# AFE.net
KiCad netlist of a schematic drawn in Altium Designer
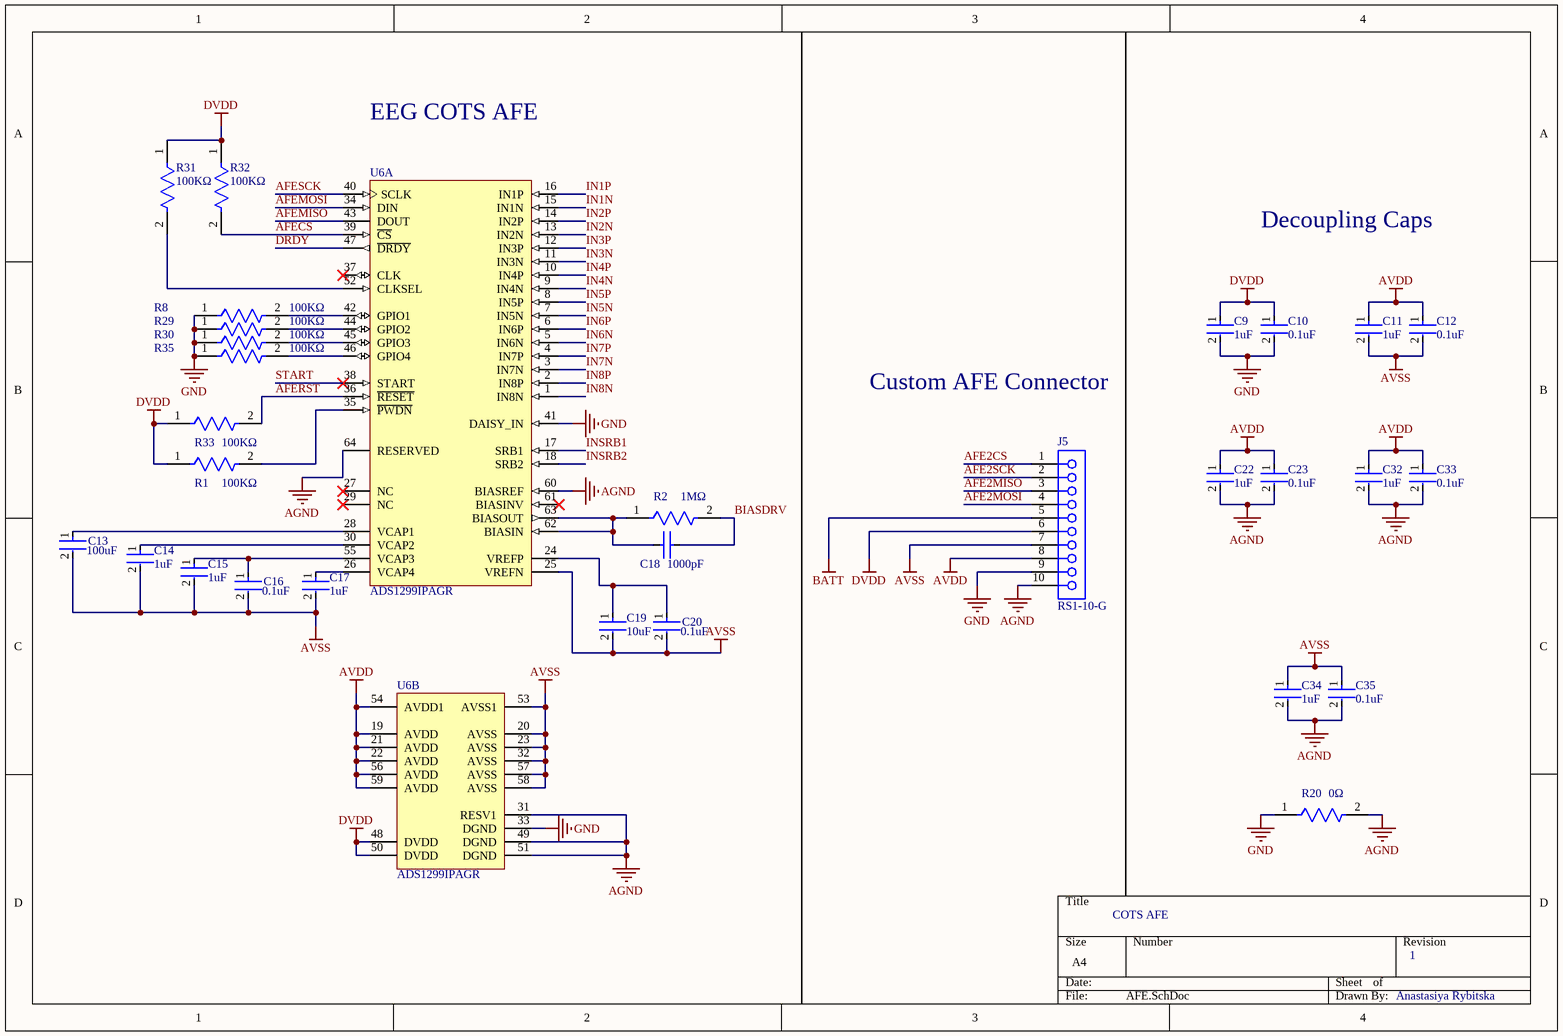
[diagram p0: AFE.SchDoc]

(export (version "E")
  (design (tool "Eeschema 10.0.6"))
  (components
    (comp (ref "C9")
      (value "CL10A105KA8NNNC")
      (footprint "FP-CL10-IPC_C")
      (description "Cap Ceramic 1uF 25V X5R ±10% Pad SMD 0603 +85°C T/R")
      (fields
        (field (name "CAPACITANCE") "1uF")
        (field (name "VOLTAGE") "25V")
        (field (name "TOLERANCE") "10%")
      )
      (libsource (lib "Altium Content Vault") (part "b4654b650e69147ec39a6b967a45e02"))
    )
    (comp (ref "C10")
      (value "KGM15BR71H104JT")
      (footprint "FP-0603-L_1_6_0_15-W_0_81-MFG")
      (description "KGM15BR71H104JT Cap Cer 0.1UF 50V X7R 0603")
      (fields (field (name "CAPACITANCE") "0.1uF") (field (name "TOLERANCE") "5%"))
      (libsource (lib "Altium Content Vault") (part "b4654b650e69147ec39a6b967a45e02"))
    )
    (comp (ref "C11")
      (value "CL10A105KA8NNNC")
      (footprint "FP-CL10-IPC_C")
      (description "Cap Ceramic 1uF 25V X5R ±10% Pad SMD 0603 +85°C T/R")
      (fields
        (field (name "CAPACITANCE") "1uF")
        (field (name "VOLTAGE") "25V")
        (field (name "TOLERANCE") "10%")
      )
      (libsource (lib "Altium Content Vault") (part "b4654b650e69147ec39a6b967a45e02"))
    )
    (comp (ref "C12")
      (value "KGM15BR71H104JT")
      (footprint "FP-0603-L_1_6_0_15-W_0_81-MFG")
      (description "KGM15BR71H104JT Cap Cer 0.1UF 50V X7R 0603")
      (fields (field (name "CAPACITANCE") "0.1uF") (field (name "TOLERANCE") "5%"))
      (libsource (lib "Altium Content Vault") (part "b4654b650e69147ec39a6b967a45e02"))
    )
    (comp (ref "C13")
      (value "GRM21BR60E107ME15K")
      (footprint "FP-GRM21B-0_2-e0_2_0_7-IPC_A")
      (description "Chip Multilayer Ceramic Capacitors for General Purpose, 0805, 100uF, X5R, 15%, 20%, 2.5V")
      (fields (field (name "CAPACITANCE") "100uF") (field (name "TOLERANCE") "20%"))
      (libsource (lib "Altium Content Vault") (part "b4654b650e69147ec39a6b967a45e02"))
    )
    (comp (ref "C14")
      (value "CL10A105KA8NNNC")
      (footprint "FP-CL10-IPC_C")
      (description "Cap Ceramic 1uF 25V X5R ±10% Pad SMD 0603 +85°C T/R")
      (fields
        (field (name "CAPACITANCE") "1uF")
        (field (name "VOLTAGE") "25V")
        (field (name "TOLERANCE") "10%")
      )
      (libsource (lib "Altium Content Vault") (part "b4654b650e69147ec39a6b967a45e02"))
    )
    (comp (ref "C15")
      (value "CL10A105KA8NNNC")
      (footprint "FP-CL10-IPC_C")
      (description "Cap Ceramic 1uF 25V X5R ±10% Pad SMD 0603 +85°C T/R")
      (fields
        (field (name "CAPACITANCE") "1uF")
        (field (name "VOLTAGE") "25V")
        (field (name "TOLERANCE") "10%")
      )
      (libsource (lib "Altium Content Vault") (part "b4654b650e69147ec39a6b967a45e02"))
    )
    (comp (ref "C16")
      (value "KGM15BR71H104JT")
      (footprint "FP-0603-L_1_6_0_15-W_0_81-MFG")
      (description "KGM15BR71H104JT Cap Cer 0.1UF 50V X7R 0603")
      (fields (field (name "CAPACITANCE") "0.1uF") (field (name "TOLERANCE") "5%"))
      (libsource (lib "Altium Content Vault") (part "b4654b650e69147ec39a6b967a45e02"))
    )
    (comp (ref "C17")
      (value "CL10A105KA8NNNC")
      (footprint "FP-CL10-IPC_C")
      (description "Cap Ceramic 1uF 25V X5R ±10% Pad SMD 0603 +85°C T/R")
      (fields
        (field (name "CAPACITANCE") "1uF")
        (field (name "VOLTAGE") "25V")
        (field (name "TOLERANCE") "10%")
      )
      (libsource (lib "Altium Content Vault") (part "b4654b650e69147ec39a6b967a45e02"))
    )
    (comp (ref "C18")
      (value "0603N102F500CT")
      (footprint "CAP_0603_S_WAL")
      (description "No Description Available")
      (fields
        (field (name "CAPACITANCE") "1000pF")
        (field (name "COPYRIGHT") "Copyright (C) 2023 Ultra Librarian. All rights reserved.")
      )
      (libsource (lib "Schlib1") (part "0603N102F500CT"))
    )
    (comp (ref "C19")
      (value "CL10A106MQ8NNNC")
      (footprint "FP-CL10-IPC_C")
      (description "Cap Ceramic 10uF 6.3V X5R ±20% Pad SMD 0603 +85°C T/R")
      (fields
        (field (name "CAPACITANCE") "10uF")
        (field (name "VOLTAGE") "6.3V")
        (field (name "TOLERANCE") "20%")
      )
      (libsource (lib "Altium Content Vault") (part "b4654b650e69147ec39a6b967a45e02"))
    )
    (comp (ref "C20")
      (value "KGM15BR71H104JT")
      (footprint "FP-0603-L_1_6_0_15-W_0_81-MFG")
      (description "KGM15BR71H104JT Cap Cer 0.1UF 50V X7R 0603")
      (fields (field (name "CAPACITANCE") "0.1uF") (field (name "TOLERANCE") "5%"))
      (libsource (lib "Altium Content Vault") (part "b4654b650e69147ec39a6b967a45e02"))
    )
    (comp (ref "C22")
      (value "CL10A105KA8NNNC")
      (footprint "FP-CL10-IPC_C")
      (description "Cap Ceramic 1uF 25V X5R ±10% Pad SMD 0603 +85°C T/R")
      (fields
        (field (name "CAPACITANCE") "1uF")
        (field (name "VOLTAGE") "25V")
        (field (name "TOLERANCE") "10%")
      )
      (libsource (lib "Altium Content Vault") (part "b4654b650e69147ec39a6b967a45e02"))
    )
    (comp (ref "C23")
      (value "KGM15BR71H104JT")
      (footprint "FP-0603-L_1_6_0_15-W_0_81-MFG")
      (description "KGM15BR71H104JT Cap Cer 0.1UF 50V X7R 0603")
      (fields (field (name "CAPACITANCE") "0.1uF") (field (name "TOLERANCE") "5%"))
      (libsource (lib "Altium Content Vault") (part "b4654b650e69147ec39a6b967a45e02"))
    )
    (comp (ref "C32")
      (value "CL10A105KA8NNNC")
      (footprint "FP-CL10-IPC_C")
      (description "Cap Ceramic 1uF 25V X5R ±10% Pad SMD 0603 +85°C T/R")
      (fields
        (field (name "CAPACITANCE") "1uF")
        (field (name "VOLTAGE") "25V")
        (field (name "TOLERANCE") "10%")
      )
      (libsource (lib "Altium Content Vault") (part "b4654b650e69147ec39a6b967a45e02"))
    )
    (comp (ref "C33")
      (value "KGM15BR71H104JT")
      (footprint "FP-0603-L_1_6_0_15-W_0_81-MFG")
      (description "KGM15BR71H104JT Cap Cer 0.1UF 50V X7R 0603")
      (fields (field (name "CAPACITANCE") "0.1uF") (field (name "TOLERANCE") "5%"))
      (libsource (lib "Altium Content Vault") (part "b4654b650e69147ec39a6b967a45e02"))
    )
    (comp (ref "C34")
      (value "CL10A105KA8NNNC")
      (footprint "FP-CL10-IPC_C")
      (description "Cap Ceramic 1uF 25V X5R ±10% Pad SMD 0603 +85°C T/R")
      (fields
        (field (name "CAPACITANCE") "1uF")
        (field (name "VOLTAGE") "25V")
        (field (name "TOLERANCE") "10%")
      )
      (libsource (lib "Altium Content Vault") (part "b4654b650e69147ec39a6b967a45e02"))
    )
    (comp (ref "C35")
      (value "KGM15BR71H104JT")
      (footprint "FP-0603-L_1_6_0_15-W_0_81-MFG")
      (description "KGM15BR71H104JT Cap Cer 0.1UF 50V X7R 0603")
      (fields (field (name "CAPACITANCE") "0.1uF") (field (name "TOLERANCE") "5%"))
      (libsource (lib "Altium Content Vault") (part "b4654b650e69147ec39a6b967a45e02"))
    )
    (comp (ref "J5")
      (value "RS1-10-G")
      (footprint "61301011821")
      (libsource (lib "Altium Content Vault") (part "Header_Female_1R_10P"))
    )
    (comp (ref "R1")
      (value "RMCF0603FT100K")
      (footprint "FP-RMCF0603-IPC_C")
      (description "100kΩ ±1% 0.1W 0603 Thick Film Chip Resistor AEC-Q200 compliant")
      (fields (field (name "TOLERANCE") "1%") (field (name "RESISTANCE") "100KΩ"))
      (libsource (lib "Altium Content Vault") (part "1029c3af85768c4190bb7ad29bc67b5"))
    )
    (comp (ref "R2")
      (value "ERJ-3EKF1004V")
      (footprint "FP-ERJ3EK-IPC_C")
      (description "RES SMD 1M OHM 1% 1/10W 0603")
      (fields (field (name "TOLERANCE") "1%") (field (name "RESISTANCE") "1MΩ"))
      (libsource (lib "Altium Content Vault") (part "1029c3af85768c4190bb7ad29bc67b5"))
    )
    (comp (ref "R8")
      (value "RMCF0603FT100K")
      (footprint "FP-RMCF0603-IPC_C")
      (description "100kΩ ±1% 0.1W 0603 Thick Film Chip Resistor AEC-Q200 compliant")
      (fields (field (name "TOLERANCE") "1%") (field (name "RESISTANCE") "100KΩ"))
      (libsource (lib "Altium Content Vault") (part "1029c3af85768c4190bb7ad29bc67b5"))
    )
    (comp (ref "R20")
      (value "RMCF0603ZT0R00")
      (footprint "FP-RMCF0603-MFG")
      (description "RES 0 OHM JUMPER 1/10W 0603")
      (fields
        (field (name "OCTOPART") "https://octopart.com/rmcf0603zt0r00-stackpole+electronics-19213618")
        (field (name "MANUFACTURER") "Stackpole")
        (field (name "RESISTANCE") "0Ω")
      )
      (libsource (lib "Altium Content Vault") (part "1029c3af85768c4190bb7ad29bc67b5"))
    )
    (comp (ref "R29")
      (value "RMCF0603FT100K")
      (footprint "FP-RMCF0603-IPC_C")
      (description "100kΩ ±1% 0.1W 0603 Thick Film Chip Resistor AEC-Q200 compliant")
      (fields (field (name "TOLERANCE") "1%") (field (name "RESISTANCE") "100KΩ"))
      (libsource (lib "Altium Content Vault") (part "1029c3af85768c4190bb7ad29bc67b5"))
    )
    (comp (ref "R30")
      (value "RMCF0603FT100K")
      (footprint "FP-RMCF0603-IPC_C")
      (description "100kΩ ±1% 0.1W 0603 Thick Film Chip Resistor AEC-Q200 compliant")
      (fields (field (name "TOLERANCE") "1%") (field (name "RESISTANCE") "100KΩ"))
      (libsource (lib "Altium Content Vault") (part "1029c3af85768c4190bb7ad29bc67b5"))
    )
    (comp (ref "R31")
      (value "RMCF0603FT100K")
      (footprint "FP-RMCF0603-IPC_C")
      (description "100kΩ ±1% 0.1W 0603 Thick Film Chip Resistor AEC-Q200 compliant")
      (fields (field (name "TOLERANCE") "1%") (field (name "RESISTANCE") "100KΩ"))
      (libsource (lib "Altium Content Vault") (part "1029c3af85768c4190bb7ad29bc67b5"))
    )
    (comp (ref "R32")
      (value "RMCF0603FT100K")
      (footprint "FP-RMCF0603-IPC_C")
      (description "100kΩ ±1% 0.1W 0603 Thick Film Chip Resistor AEC-Q200 compliant")
      (fields (field (name "TOLERANCE") "1%") (field (name "RESISTANCE") "100KΩ"))
      (libsource (lib "Altium Content Vault") (part "1029c3af85768c4190bb7ad29bc67b5"))
    )
    (comp (ref "R33")
      (value "RMCF0603FT100K")
      (footprint "FP-RMCF0603-IPC_C")
      (description "100kΩ ±1% 0.1W 0603 Thick Film Chip Resistor AEC-Q200 compliant")
      (fields (field (name "TOLERANCE") "1%") (field (name "RESISTANCE") "100KΩ"))
      (libsource (lib "Altium Content Vault") (part "1029c3af85768c4190bb7ad29bc67b5"))
    )
    (comp (ref "R35")
      (value "RMCF0603FT100K")
      (footprint "FP-RMCF0603-IPC_C")
      (description "100kΩ ±1% 0.1W 0603 Thick Film Chip Resistor AEC-Q200 compliant")
      (fields (field (name "TOLERANCE") "1%") (field (name "RESISTANCE") "100KΩ"))
      (libsource (lib "Altium Content Vault") (part "1029c3af85768c4190bb7ad29bc67b5"))
    )
    (comp (ref "U6")
      (value "ADS1299IPAGR")
      (footprint "PAG0064A_M")
      (fields (field (name "MANUFACTURER") "Texas Instruments"))
      (libsource (lib "Altium Content Vault") (part "TI-ADS1299-PAG-64"))
    )
  )
  (nets
    (net (code "1") (name "/AFE2CS") (class "Default")
      (node (ref "J5") (pin "1") (pinfunction "1_1") (pintype "passive"))
    )
    (net (code "2") (name "/AFE2MISO") (class "Default")
      (node (ref "J5") (pin "3") (pinfunction "3_3") (pintype "passive"))
    )
    (net (code "3") (name "/AFE2MOSI") (class "Default")
      (node (ref "J5") (pin "4") (pinfunction "4_4") (pintype "passive"))
    )
    (net (code "4") (name "/AFE2SCK") (class "Default")
      (node (ref "J5") (pin "2") (pinfunction "2_2") (pintype "passive"))
    )
    (net (code "5") (name "/AFECS") (class "Default")
      (node (ref "R32") (pin "2") (pinfunction "2_2") (pintype "passive"))
      (node (ref "U6") (pin "39") (pinfunction "~{CS}_39") (pintype "input"))
    )
    (net (code "6") (name "/AFEMISO") (class "Default")
      (node (ref "U6") (pin "43") (pinfunction "DOUT_43") (pintype "tri_state"))
    )
    (net (code "7") (name "/AFEMOSI") (class "Default")
      (node (ref "U6") (pin "34") (pinfunction "DIN_34") (pintype "input"))
    )
    (net (code "8") (name "/AFERST") (class "Default")
      (node (ref "R33") (pin "2") (pinfunction "2_2") (pintype "passive"))
      (node (ref "U6") (pin "36") (pinfunction "~{RESET}_36") (pintype "input"))
    )
    (net (code "9") (name "/AFESCK") (class "Default")
      (node (ref "U6") (pin "40") (pinfunction "SCLK_40") (pintype "input"))
    )
    (net (code "10") (name "/BIASDRV") (class "Default")
      (node (ref "C18") (pin "2") (pinfunction "2_2") (pintype "passive"))
      (node (ref "R2") (pin "2") (pinfunction "2_2") (pintype "passive"))
    )
    (net (code "11") (name "/DRDY") (class "Default")
      (node (ref "U6") (pin "47") (pinfunction "~{DRDY}_47") (pintype "output"))
    )
    (net (code "12") (name "/IN1N") (class "Default")
      (node (ref "U6") (pin "15") (pinfunction "IN1N_15") (pintype "input"))
    )
    (net (code "13") (name "/IN1P") (class "Default")
      (node (ref "U6") (pin "16") (pinfunction "IN1P_16") (pintype "input"))
    )
    (net (code "14") (name "/IN2N") (class "Default")
      (node (ref "U6") (pin "13") (pinfunction "IN2N_13") (pintype "input"))
    )
    (net (code "15") (name "/IN2P") (class "Default")
      (node (ref "U6") (pin "14") (pinfunction "IN2P_14") (pintype "input"))
    )
    (net (code "16") (name "/IN3N") (class "Default")
      (node (ref "U6") (pin "11") (pinfunction "IN3N_11") (pintype "input"))
    )
    (net (code "17") (name "/IN3P") (class "Default")
      (node (ref "U6") (pin "12") (pinfunction "IN3P_12") (pintype "input"))
    )
    (net (code "18") (name "/IN4N") (class "Default")
      (node (ref "U6") (pin "9") (pinfunction "IN4N_9") (pintype "input"))
    )
    (net (code "19") (name "/IN4P") (class "Default")
      (node (ref "U6") (pin "10") (pinfunction "IN4P_10") (pintype "input"))
    )
    (net (code "20") (name "/IN5N") (class "Default")
      (node (ref "U6") (pin "7") (pinfunction "IN5N_7") (pintype "input"))
    )
    (net (code "21") (name "/IN5P") (class "Default")
      (node (ref "U6") (pin "8") (pinfunction "IN5P_8") (pintype "input"))
    )
    (net (code "22") (name "/IN6N") (class "Default")
      (node (ref "U6") (pin "5") (pinfunction "IN6N_5") (pintype "input"))
    )
    (net (code "23") (name "/IN6P") (class "Default")
      (node (ref "U6") (pin "6") (pinfunction "IN6P_6") (pintype "input"))
    )
    (net (code "24") (name "/IN7N") (class "Default")
      (node (ref "U6") (pin "3") (pinfunction "IN7N_3") (pintype "input"))
    )
    (net (code "25") (name "/IN7P") (class "Default")
      (node (ref "U6") (pin "4") (pinfunction "IN7P_4") (pintype "input"))
    )
    (net (code "26") (name "/IN8N") (class "Default")
      (node (ref "U6") (pin "1") (pinfunction "IN8N_1") (pintype "input"))
    )
    (net (code "27") (name "/IN8P") (class "Default")
      (node (ref "U6") (pin "2") (pinfunction "IN8P_2") (pintype "input"))
    )
    (net (code "28") (name "/INSRB1") (class "Default")
      (node (ref "U6") (pin "17") (pinfunction "SRB1_17") (pintype "input"))
    )
    (net (code "29") (name "/INSRB2") (class "Default")
      (node (ref "U6") (pin "18") (pinfunction "SRB2_18") (pintype "input"))
    )
    (net (code "30") (name "/START") (class "Default")
      (node (ref "U6") (pin "38") (pinfunction "START_38") (pintype "input+no_connect"))
    )
    (net (code "31") (name "AGND") (class "Default")
      (node (ref "C22") (pin "2") (pinfunction "2_2") (pintype "passive"))
      (node (ref "C23") (pin "2") (pinfunction "2_2") (pintype "passive"))
      (node (ref "C32") (pin "2") (pinfunction "2_2") (pintype "passive"))
      (node (ref "C33") (pin "2") (pinfunction "2_2") (pintype "passive"))
      (node (ref "C34") (pin "2") (pinfunction "2_2") (pintype "passive"))
      (node (ref "C35") (pin "2") (pinfunction "2_2") (pintype "passive"))
      (node (ref "J5") (pin "10") (pinfunction "10_10") (pintype "passive"))
      (node (ref "R20") (pin "2") (pinfunction "2_2") (pintype "passive"))
      (node (ref "U6") (pin "31") (pinfunction "RESV1_31") (pintype "power_in"))
      (node (ref "U6") (pin "49") (pinfunction "DGND_49") (pintype "power_in"))
      (node (ref "U6") (pin "51") (pinfunction "DGND_51") (pintype "power_in"))
      (node (ref "U6") (pin "60") (pinfunction "BIASREF_60") (pintype "input"))
      (node (ref "U6") (pin "64") (pinfunction "RESERVED_64") (pintype "passive"))
    )
    (net (code "32") (name "AVDD") (class "Default")
      (node (ref "C11") (pin "1") (pinfunction "1_1") (pintype "passive"))
      (node (ref "C12") (pin "1") (pinfunction "1_1") (pintype "passive"))
      (node (ref "C22") (pin "1") (pinfunction "1_1") (pintype "passive"))
      (node (ref "C23") (pin "1") (pinfunction "1_1") (pintype "passive"))
      (node (ref "C32") (pin "1") (pinfunction "1_1") (pintype "passive"))
      (node (ref "C33") (pin "1") (pinfunction "1_1") (pintype "passive"))
      (node (ref "J5") (pin "8") (pinfunction "8_8") (pintype "passive"))
      (node (ref "U6") (pin "19") (pinfunction "AVDD_19") (pintype "power_in"))
      (node (ref "U6") (pin "21") (pinfunction "AVDD_21") (pintype "power_in"))
      (node (ref "U6") (pin "22") (pinfunction "AVDD_22") (pintype "power_in"))
      (node (ref "U6") (pin "54") (pinfunction "AVDD1_54") (pintype "power_in"))
      (node (ref "U6") (pin "56") (pinfunction "AVDD_56") (pintype "power_in"))
      (node (ref "U6") (pin "59") (pinfunction "AVDD_59") (pintype "power_in"))
    )
    (net (code "33") (name "AVSS") (class "Default")
      (node (ref "C11") (pin "2") (pinfunction "2_2") (pintype "passive"))
      (node (ref "C12") (pin "2") (pinfunction "2_2") (pintype "passive"))
      (node (ref "C13") (pin "2") (pinfunction "2_2") (pintype "passive"))
      (node (ref "C14") (pin "2") (pinfunction "2_2") (pintype "passive"))
      (node (ref "C15") (pin "2") (pinfunction "2_2") (pintype "passive"))
      (node (ref "C16") (pin "2") (pinfunction "2_2") (pintype "passive"))
      (node (ref "C17") (pin "2") (pinfunction "2_2") (pintype "passive"))
      (node (ref "C19") (pin "2") (pinfunction "2_2") (pintype "passive"))
      (node (ref "C20") (pin "2") (pinfunction "2_2") (pintype "passive"))
      (node (ref "C34") (pin "1") (pinfunction "1_1") (pintype "passive"))
      (node (ref "C35") (pin "1") (pinfunction "1_1") (pintype "passive"))
      (node (ref "J5") (pin "7") (pinfunction "7_7") (pintype "passive"))
      (node (ref "U6") (pin "20") (pinfunction "AVSS_20") (pintype "power_in"))
      (node (ref "U6") (pin "23") (pinfunction "AVSS_23") (pintype "power_in"))
      (node (ref "U6") (pin "25") (pinfunction "VREFN_25") (pintype "passive"))
      (node (ref "U6") (pin "32") (pinfunction "AVSS_32") (pintype "power_in"))
      (node (ref "U6") (pin "53") (pinfunction "AVSS1_53") (pintype "power_in"))
      (node (ref "U6") (pin "57") (pinfunction "AVSS_57") (pintype "power_in"))
      (node (ref "U6") (pin "58") (pinfunction "AVSS_58") (pintype "power_in"))
    )
    (net (code "34") (name "BATT") (class "Default")
      (node (ref "J5") (pin "5") (pinfunction "5_5") (pintype "passive"))
    )
    (net (code "35") (name "DVDD") (class "Default")
      (node (ref "C10") (pin "1") (pinfunction "1_1") (pintype "passive"))
      (node (ref "C9") (pin "1") (pinfunction "1_1") (pintype "passive"))
      (node (ref "J5") (pin "6") (pinfunction "6_6") (pintype "passive"))
      (node (ref "R1") (pin "1") (pinfunction "1_1") (pintype "passive"))
      (node (ref "R31") (pin "1") (pinfunction "1_1") (pintype "passive"))
      (node (ref "R32") (pin "1") (pinfunction "1_1") (pintype "passive"))
      (node (ref "R33") (pin "1") (pinfunction "1_1") (pintype "passive"))
      (node (ref "U6") (pin "48") (pinfunction "DVDD_48") (pintype "power_in"))
      (node (ref "U6") (pin "50") (pinfunction "DVDD_50") (pintype "power_in"))
    )
    (net (code "36") (name "GND") (class "Default")
      (node (ref "C10") (pin "2") (pinfunction "2_2") (pintype "passive"))
      (node (ref "C9") (pin "2") (pinfunction "2_2") (pintype "passive"))
      (node (ref "J5") (pin "9") (pinfunction "9_9") (pintype "passive"))
      (node (ref "R20") (pin "1") (pinfunction "1_1") (pintype "passive"))
      (node (ref "R29") (pin "1") (pinfunction "1_1") (pintype "passive"))
      (node (ref "R30") (pin "1") (pinfunction "1_1") (pintype "passive"))
      (node (ref "R35") (pin "1") (pinfunction "1_1") (pintype "passive"))
      (node (ref "R8") (pin "1") (pinfunction "1_1") (pintype "passive"))
      (node (ref "U6") (pin "33") (pinfunction "DGND_33") (pintype "power_in"))
      (node (ref "U6") (pin "41") (pinfunction "DAISY_IN_41") (pintype "input"))
    )
    (net (code "37") (name "Net-(U6A-BIASIN)") (class "Default")
      (node (ref "C18") (pin "1") (pinfunction "1_1") (pintype "passive"))
      (node (ref "R2") (pin "1") (pinfunction "1_1") (pintype "passive"))
      (node (ref "U6") (pin "62") (pinfunction "BIASIN_62") (pintype "input"))
      (node (ref "U6") (pin "63") (pinfunction "BIASOUT_63") (pintype "output"))
    )
    (net (code "38") (name "Net-(U6A-CLKSEL)") (class "Default")
      (node (ref "R31") (pin "2") (pinfunction "2_2") (pintype "passive"))
      (node (ref "U6") (pin "52") (pinfunction "CLKSEL_52") (pintype "input"))
    )
    (net (code "39") (name "Net-(U6A-GPIO1)") (class "Default")
      (node (ref "R8") (pin "2") (pinfunction "2_2") (pintype "passive"))
      (node (ref "U6") (pin "42") (pinfunction "GPIO1_42") (pintype "bidirectional"))
    )
    (net (code "40") (name "Net-(U6A-GPIO2)") (class "Default")
      (node (ref "R29") (pin "2") (pinfunction "2_2") (pintype "passive"))
      (node (ref "U6") (pin "44") (pinfunction "GPIO2_44") (pintype "bidirectional"))
    )
    (net (code "41") (name "Net-(U6A-GPIO3)") (class "Default")
      (node (ref "R30") (pin "2") (pinfunction "2_2") (pintype "passive"))
      (node (ref "U6") (pin "45") (pinfunction "GPIO3_45") (pintype "bidirectional"))
    )
    (net (code "42") (name "Net-(U6A-GPIO4)") (class "Default")
      (node (ref "R35") (pin "2") (pinfunction "2_2") (pintype "passive"))
      (node (ref "U6") (pin "46") (pinfunction "GPIO4_46") (pintype "bidirectional"))
    )
    (net (code "43") (name "Net-(U6A-VCAP1)") (class "Default")
      (node (ref "C13") (pin "1") (pinfunction "1_1") (pintype "passive"))
      (node (ref "U6") (pin "28") (pinfunction "VCAP1_28") (pintype "passive"))
    )
    (net (code "44") (name "Net-(U6A-VCAP2)") (class "Default")
      (node (ref "C14") (pin "1") (pinfunction "1_1") (pintype "passive"))
      (node (ref "U6") (pin "30") (pinfunction "VCAP2_30") (pintype "passive"))
    )
    (net (code "45") (name "Net-(U6A-VCAP3)") (class "Default")
      (node (ref "C15") (pin "1") (pinfunction "1_1") (pintype "passive"))
      (node (ref "C16") (pin "1") (pinfunction "1_1") (pintype "passive"))
      (node (ref "U6") (pin "55") (pinfunction "VCAP3_55") (pintype "passive"))
    )
    (net (code "46") (name "Net-(U6A-VCAP4)") (class "Default")
      (node (ref "C17") (pin "1") (pinfunction "1_1") (pintype "passive"))
      (node (ref "U6") (pin "26") (pinfunction "VCAP4_26") (pintype "passive"))
    )
    (net (code "47") (name "Net-(U6A-VREFP)") (class "Default")
      (node (ref "C19") (pin "1") (pinfunction "1_1") (pintype "passive"))
      (node (ref "C20") (pin "1") (pinfunction "1_1") (pintype "passive"))
      (node (ref "U6") (pin "24") (pinfunction "VREFP_24") (pintype "passive"))
    )
    (net (code "48") (name "Net-(U6A-~{PWDN})") (class "Default")
      (node (ref "R1") (pin "2") (pinfunction "2_2") (pintype "passive"))
      (node (ref "U6") (pin "35") (pinfunction "~{PWDN}_35") (pintype "input"))
    )
    (net (code "49") (name "unconnected-(U6A-BIASINV-Pad61)") (class "Default")
      (node (ref "U6") (pin "61") (pinfunction "BIASINV_61") (pintype "input+no_connect"))
    )
    (net (code "50") (name "unconnected-(U6A-CLK-Pad37)") (class "Default")
      (node (ref "U6") (pin "37") (pinfunction "CLK_37") (pintype "bidirectional+no_connect"))
    )
    (net (code "51") (name "unconnected-(U6A-NC-Pad27)") (class "Default")
      (node (ref "U6") (pin "27") (pinfunction "NC_27") (pintype "passive+no_connect"))
    )
    (net (code "52") (name "unconnected-(U6A-NC-Pad29)") (class "Default")
      (node (ref "U6") (pin "29") (pinfunction "NC_29") (pintype "passive+no_connect"))
    )
  )
)
